# Schematic_Arduino-UNO-shield-for-program.net
KiCad netlist of a schematic drawn in EasyEDA
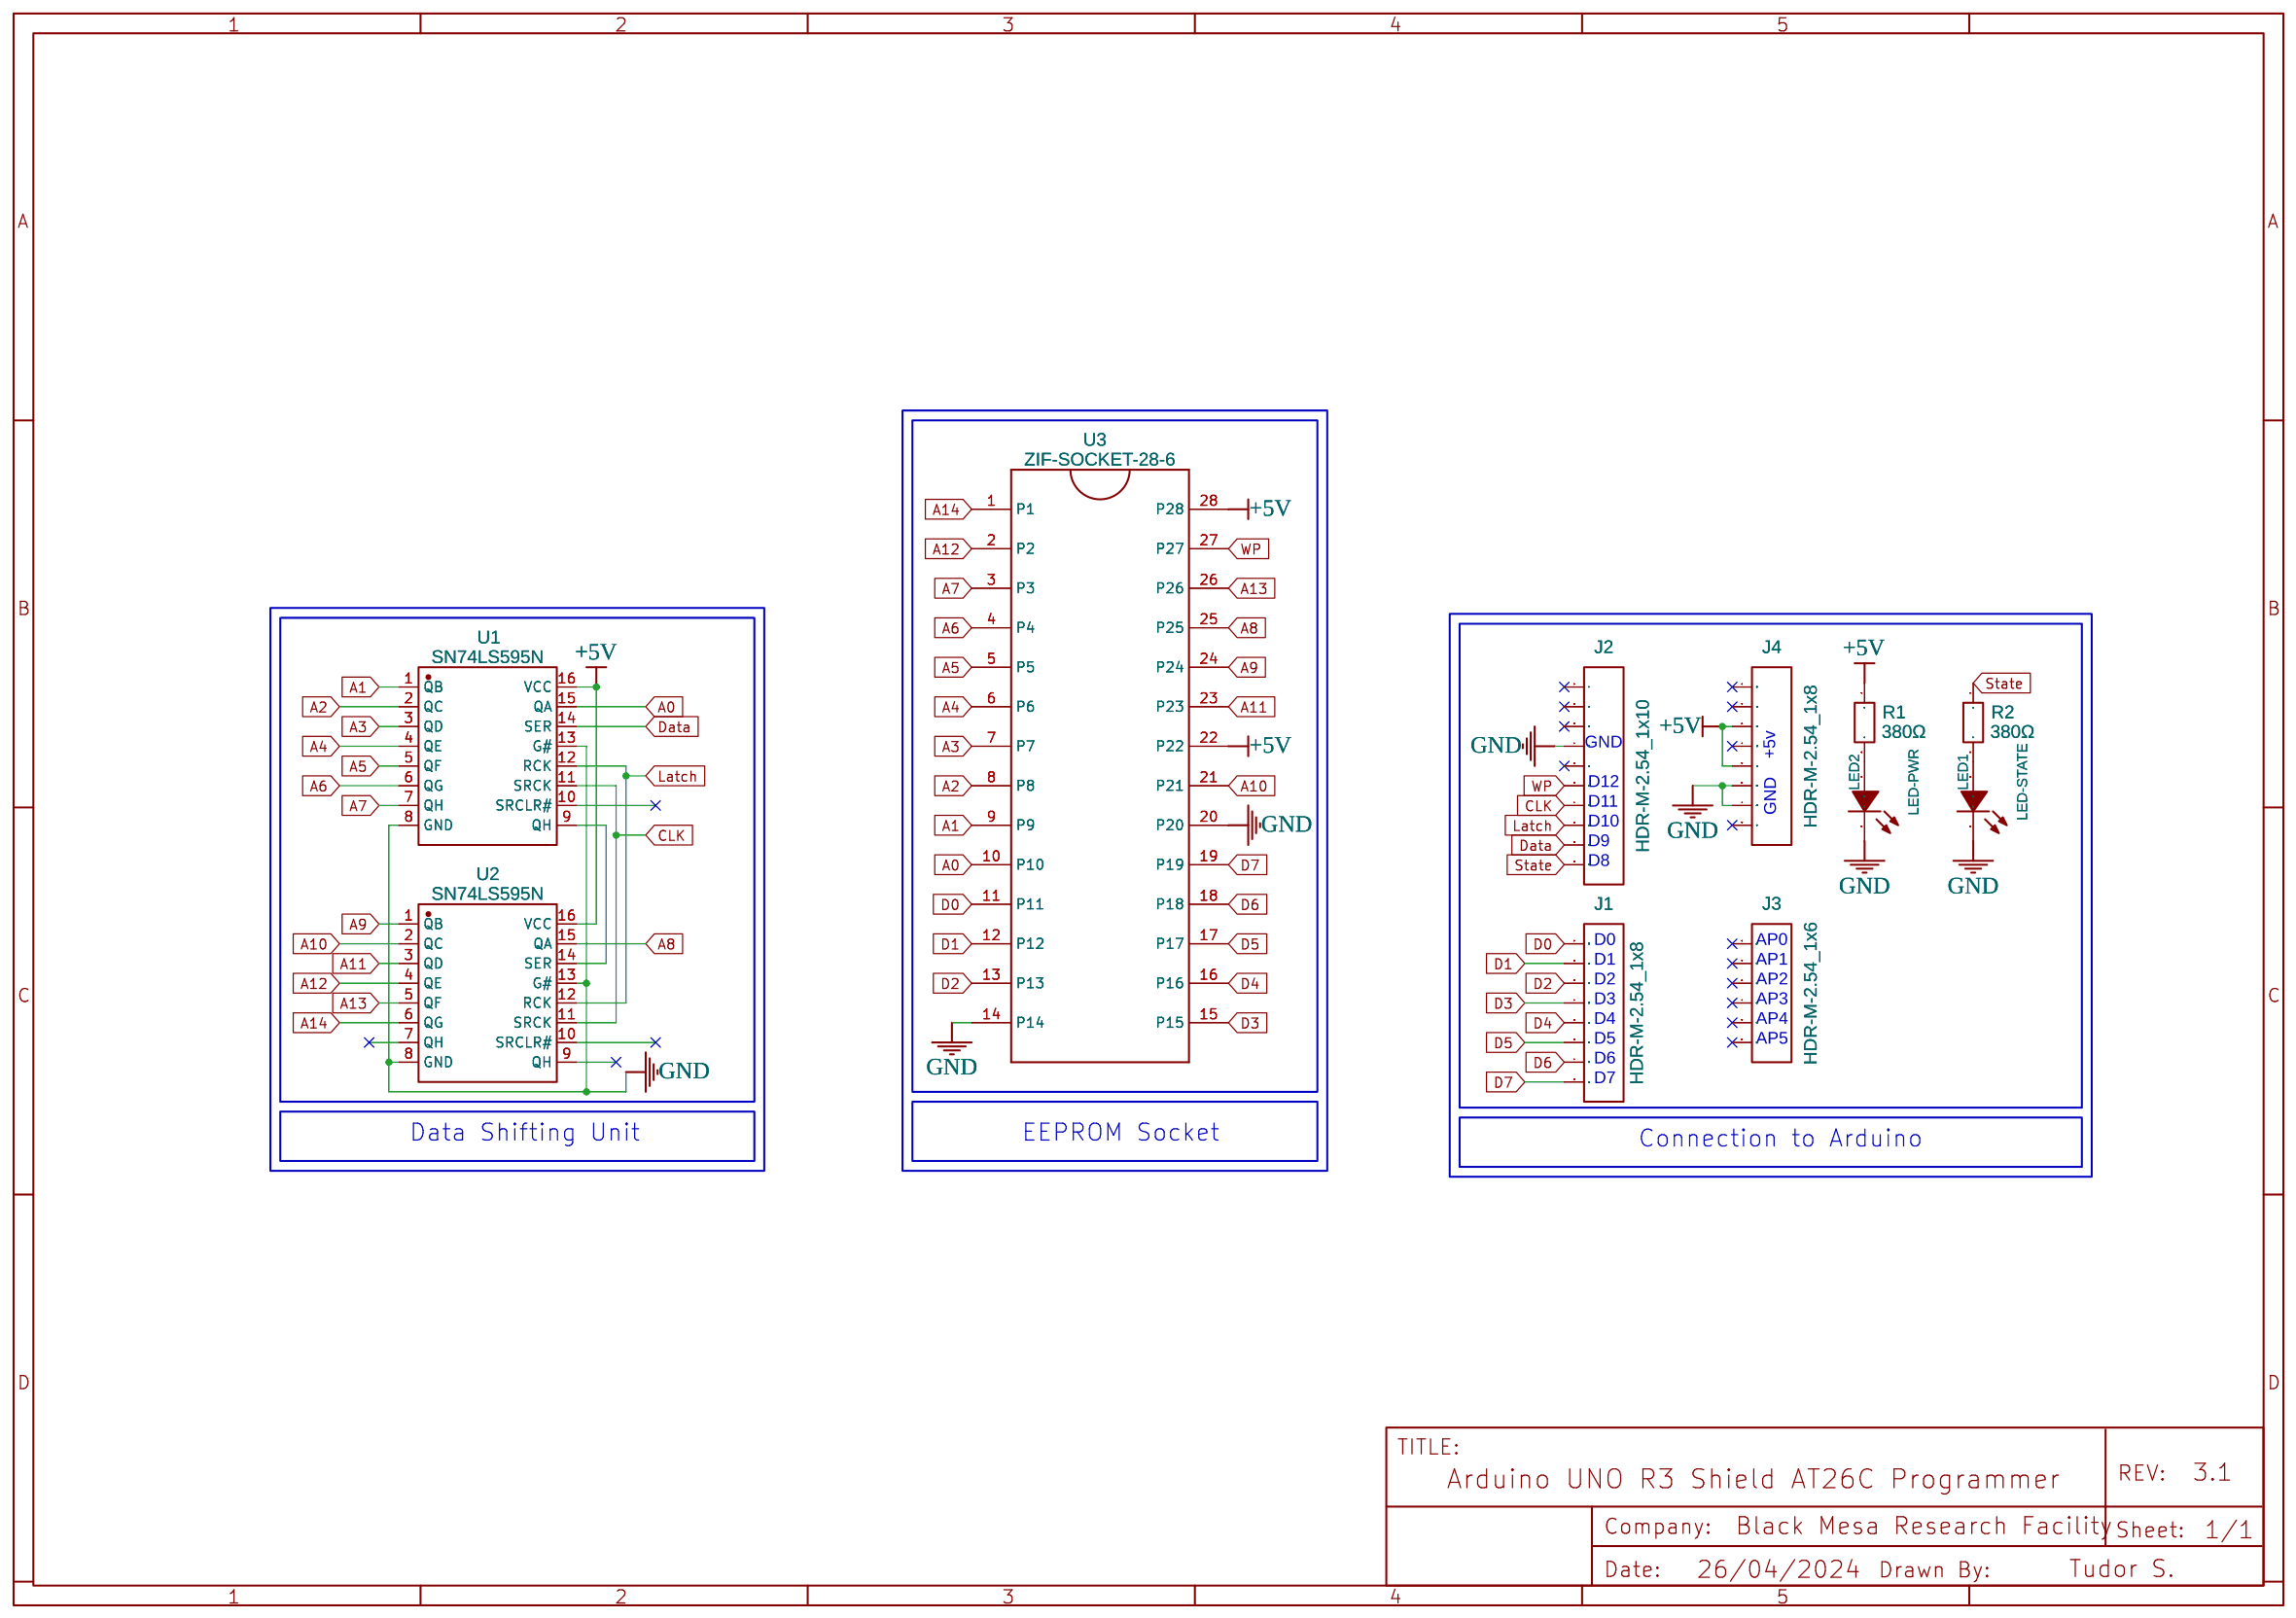
[diagram p0: schematic sheet]

(export (version "E")
  (design (tool "Eeschema 10.0.6"))
  (components
    (comp (ref "J1") (value "HDR-M-2.54_1x8") (libsource (lib "") (part "HDR-M-2.54_1x8")))
    (comp (ref "J2") (value "HDR-M-2.54_1x10") (libsource (lib "") (part "HDR-M-2.54_1x10")))
    (comp (ref "J3") (value "HDR-M-2.54_1x6") (libsource (lib "") (part "HDR-M-2.54_1x6")))
    (comp (ref "J4") (value "HDR-M-2.54_1x8") (libsource (lib "") (part "HDR-M-2.54_1x8_1")))
    (comp (ref "LED1")
      (value "LED-STATE")
      (fields
        (field (name "Manufacturer Part") "19-217/R6C-AL1M2VY/3T")
        (field (name "Manufacturer") "EVERLIGHT(台湾亿光)")
      )
      (libsource (lib "") (part "LED-0603_R"))
    )
    (comp (ref "LED2")
      (value "LED-PWR")
      (fields
        (field (name "Manufacturer Part") "19-217/R6C-AL1M2VY/3T")
        (field (name "Manufacturer") "EVERLIGHT(台湾亿光)")
      )
      (libsource (lib "") (part "LED-0603_R"))
    )
    (comp (ref "R1") (value "380Ω") (libsource (lib "") (part "R_AXIAL-0.4_EU")))
    (comp (ref "R2") (value "380Ω") (libsource (lib "") (part "R_AXIAL-0.4_EU")))
    (comp (ref "U1")
      (value "SN74LS595N")
      (fields (field (name "Manufacturer") "TI(德州仪器)"))
      (libsource (lib "") (part "SN74LS595N"))
    )
    (comp (ref "U2")
      (value "SN74LS595N")
      (fields (field (name "Manufacturer") "TI(德州仪器)"))
      (libsource (lib "") (part "SN74LS595N"))
    )
    (comp (ref "U3")
      (value "ZIF-SOCKET-28-6")
      (fields (field (name "Manufacturer Part") "ZIFSOCKET-28-6"))
      (libsource (lib "") (part "ZIF-SOCKET-28-6"))
    )
  )
  (nets
    (net (code "1") (name "+5V") (class "Default")
      (node (ref "J4") (pin "3") (pinfunction "RESET_3") (pintype "unspecified"))
      (node (ref "J4") (pin "5") (pinfunction "+5V_5") (pintype "unspecified"))
      (node (ref "R1") (pin "1") (pinfunction "1_1") (pintype "unspecified"))
      (node (ref "U1") (pin "16") (pinfunction "VCC_16") (pintype "unspecified"))
      (node (ref "U2") (pin "16") (pinfunction "VCC_16") (pintype "unspecified"))
      (node (ref "U3") (pin "22") (pinfunction "P22_22") (pintype "unspecified"))
      (node (ref "U3") (pin "28") (pinfunction "P28_28") (pintype "unspecified"))
    )
    (net (code "2") (name "A0") (class "Default")
      (node (ref "U1") (pin "15") (pinfunction "QA_15") (pintype "unspecified"))
      (node (ref "U3") (pin "10") (pinfunction "P10_10") (pintype "unspecified"))
    )
    (net (code "3") (name "A1") (class "Default")
      (node (ref "U1") (pin "1") (pinfunction "QB_1") (pintype "unspecified"))
      (node (ref "U3") (pin "9") (pinfunction "P9_9") (pintype "unspecified"))
    )
    (net (code "4") (name "A2") (class "Default")
      (node (ref "U1") (pin "2") (pinfunction "QC_2") (pintype "unspecified"))
      (node (ref "U3") (pin "8") (pinfunction "P8_8") (pintype "unspecified"))
    )
    (net (code "5") (name "A3") (class "Default")
      (node (ref "U1") (pin "3") (pinfunction "QD_3") (pintype "unspecified"))
      (node (ref "U3") (pin "7") (pinfunction "P7_7") (pintype "unspecified"))
    )
    (net (code "6") (name "A4") (class "Default")
      (node (ref "U1") (pin "4") (pinfunction "QE_4") (pintype "unspecified"))
      (node (ref "U3") (pin "6") (pinfunction "P6_6") (pintype "unspecified"))
    )
    (net (code "7") (name "A5") (class "Default")
      (node (ref "U1") (pin "5") (pinfunction "QF_5") (pintype "unspecified"))
      (node (ref "U3") (pin "5") (pinfunction "P5_5") (pintype "unspecified"))
    )
    (net (code "8") (name "A6") (class "Default")
      (node (ref "U1") (pin "6") (pinfunction "QG_6") (pintype "unspecified"))
      (node (ref "U3") (pin "4") (pinfunction "P4_4") (pintype "unspecified"))
    )
    (net (code "9") (name "A7") (class "Default")
      (node (ref "U1") (pin "7") (pinfunction "QH_7") (pintype "unspecified"))
      (node (ref "U3") (pin "3") (pinfunction "P3_3") (pintype "unspecified"))
    )
    (net (code "10") (name "A8") (class "Default")
      (node (ref "U2") (pin "15") (pinfunction "QA_15") (pintype "unspecified"))
      (node (ref "U3") (pin "25") (pinfunction "P25_25") (pintype "unspecified"))
    )
    (net (code "11") (name "A9") (class "Default")
      (node (ref "U2") (pin "1") (pinfunction "QB_1") (pintype "unspecified"))
      (node (ref "U3") (pin "24") (pinfunction "P24_24") (pintype "unspecified"))
    )
    (net (code "12") (name "A10") (class "Default")
      (node (ref "U2") (pin "2") (pinfunction "QC_2") (pintype "unspecified"))
      (node (ref "U3") (pin "21") (pinfunction "P21_21") (pintype "unspecified"))
    )
    (net (code "13") (name "A11") (class "Default")
      (node (ref "U2") (pin "3") (pinfunction "QD_3") (pintype "unspecified"))
      (node (ref "U3") (pin "23") (pinfunction "P23_23") (pintype "unspecified"))
    )
    (net (code "14") (name "A12") (class "Default")
      (node (ref "U2") (pin "4") (pinfunction "QE_4") (pintype "unspecified"))
      (node (ref "U3") (pin "2") (pinfunction "P2_2") (pintype "unspecified"))
    )
    (net (code "15") (name "A13") (class "Default")
      (node (ref "U2") (pin "5") (pinfunction "QF_5") (pintype "unspecified"))
      (node (ref "U3") (pin "26") (pinfunction "P26_26") (pintype "unspecified"))
    )
    (net (code "16") (name "A14") (class "Default")
      (node (ref "U2") (pin "6") (pinfunction "QG_6") (pintype "unspecified"))
      (node (ref "U3") (pin "1") (pinfunction "P1_1") (pintype "unspecified"))
    )
    (net (code "17") (name "CLK") (class "Default")
      (node (ref "J2") (pin "7") (pinfunction "D11_7") (pintype "unspecified"))
      (node (ref "U1") (pin "11") (pinfunction "SRCK_11") (pintype "unspecified"))
      (node (ref "U2") (pin "11") (pinfunction "SRCK_11") (pintype "unspecified"))
    )
    (net (code "18") (name "D0") (class "Default")
      (node (ref "J1") (pin "1") (pinfunction "D0_1") (pintype "unspecified"))
      (node (ref "U3") (pin "11") (pinfunction "P11_11") (pintype "unspecified"))
    )
    (net (code "19") (name "D1") (class "Default")
      (node (ref "J1") (pin "2") (pinfunction "D1_2") (pintype "unspecified"))
      (node (ref "U3") (pin "12") (pinfunction "P12_12") (pintype "unspecified"))
    )
    (net (code "20") (name "D2") (class "Default")
      (node (ref "J1") (pin "3") (pinfunction "D2_3") (pintype "unspecified"))
      (node (ref "U3") (pin "13") (pinfunction "P13_13") (pintype "unspecified"))
    )
    (net (code "21") (name "D3") (class "Default")
      (node (ref "J1") (pin "4") (pinfunction "D3_4") (pintype "unspecified"))
      (node (ref "U3") (pin "15") (pinfunction "P15_15") (pintype "unspecified"))
    )
    (net (code "22") (name "D4") (class "Default")
      (node (ref "J1") (pin "5") (pinfunction "D4_5") (pintype "unspecified"))
      (node (ref "U3") (pin "16") (pinfunction "P16_16") (pintype "unspecified"))
    )
    (net (code "23") (name "D5") (class "Default")
      (node (ref "J1") (pin "6") (pinfunction "D5_6") (pintype "unspecified"))
      (node (ref "U3") (pin "17") (pinfunction "P17_17") (pintype "unspecified"))
    )
    (net (code "24") (name "D6") (class "Default")
      (node (ref "J1") (pin "7") (pinfunction "D6_7") (pintype "unspecified"))
      (node (ref "U3") (pin "18") (pinfunction "P18_18") (pintype "unspecified"))
    )
    (net (code "25") (name "D7") (class "Default")
      (node (ref "J1") (pin "8") (pinfunction "D7_8") (pintype "unspecified"))
      (node (ref "U3") (pin "19") (pinfunction "P19_19") (pintype "unspecified"))
    )
    (net (code "26") (name "Data") (class "Default")
      (node (ref "J2") (pin "9") (pinfunction "D9_9") (pintype "unspecified"))
      (node (ref "U1") (pin "14") (pinfunction "SER_14") (pintype "unspecified"))
    )
    (net (code "27") (name "GND") (class "Default")
      (node (ref "J2") (pin "4") (pinfunction "GND_4") (pintype "unspecified"))
      (node (ref "J4") (pin "6") (pinfunction "GND_6") (pintype "unspecified"))
      (node (ref "J4") (pin "7") (pinfunction "GND_7") (pintype "unspecified"))
      (node (ref "LED1") (pin "2") (pinfunction "2_2") (pintype "unspecified"))
      (node (ref "LED2") (pin "2") (pinfunction "2_2") (pintype "unspecified"))
      (node (ref "U1") (pin "13") (pinfunction "G#_13") (pintype "unspecified"))
      (node (ref "U1") (pin "8") (pinfunction "GND_8") (pintype "unspecified"))
      (node (ref "U2") (pin "13") (pinfunction "G#_13") (pintype "unspecified"))
      (node (ref "U2") (pin "8") (pinfunction "GND_8") (pintype "unspecified"))
      (node (ref "U3") (pin "14") (pinfunction "P14_14") (pintype "unspecified"))
      (node (ref "U3") (pin "20") (pinfunction "P20_20") (pintype "unspecified"))
    )
    (net (code "28") (name "Latch") (class "Default")
      (node (ref "J2") (pin "8") (pinfunction "D10_8") (pintype "unspecified"))
      (node (ref "U1") (pin "12") (pinfunction "RCK_12") (pintype "unspecified"))
      (node (ref "U2") (pin "12") (pinfunction "RCK_12") (pintype "unspecified"))
    )
    (net (code "29") (name "Net-(LED1-Pad1)") (class "Default")
      (node (ref "LED1") (pin "1") (pinfunction "1_1") (pintype "unspecified"))
      (node (ref "R2") (pin "2") (pinfunction "2_2") (pintype "unspecified"))
    )
    (net (code "30") (name "Net-(LED2-Pad1)") (class "Default")
      (node (ref "LED2") (pin "1") (pinfunction "1_1") (pintype "unspecified"))
      (node (ref "R1") (pin "2") (pinfunction "2_2") (pintype "unspecified"))
    )
    (net (code "31") (name "Net-(U2-SER)") (class "Default")
      (node (ref "U1") (pin "9") (pinfunction "QH_9") (pintype "unspecified"))
      (node (ref "U2") (pin "14") (pinfunction "SER_14") (pintype "unspecified"))
    )
    (net (code "32") (name "State") (class "Default")
      (node (ref "J2") (pin "10") (pinfunction "D8_10") (pintype "unspecified"))
      (node (ref "R2") (pin "1") (pinfunction "1_1") (pintype "unspecified"))
    )
    (net (code "33") (name "WP") (class "Default")
      (node (ref "J2") (pin "6") (pinfunction "D12_6") (pintype "unspecified"))
      (node (ref "U3") (pin "27") (pinfunction "P27_27") (pintype "unspecified"))
    )
    (net (code "34") (name "unconnected-(J2-AREF-Pad3)") (class "Default")
      (node (ref "J2") (pin "3") (pinfunction "AREF_3") (pintype "unspecified+no_connect"))
    )
    (net (code "35") (name "unconnected-(J2-D13-Pad5)") (class "Default")
      (node (ref "J2") (pin "5") (pinfunction "D13_5") (pintype "unspecified+no_connect"))
    )
    (net (code "36") (name "unconnected-(J2-Pad1)") (class "Default")
      (node (ref "J2") (pin "1") (pinfunction "1_1") (pintype "unspecified+no_connect"))
    )
    (net (code "37") (name "unconnected-(J2-Pad2)") (class "Default")
      (node (ref "J2") (pin "2") (pinfunction "2_2") (pintype "unspecified+no_connect"))
    )
    (net (code "38") (name "unconnected-(J3-S0-Pad1)") (class "Default")
      (node (ref "J3") (pin "1") (pinfunction "S0_1") (pintype "input+no_connect"))
    )
    (net (code "39") (name "unconnected-(J3-S1-Pad2)") (class "Default")
      (node (ref "J3") (pin "2") (pinfunction "S1_2") (pintype "input+no_connect"))
    )
    (net (code "40") (name "unconnected-(J3-S2-Pad3)") (class "Default")
      (node (ref "J3") (pin "3") (pinfunction "S2_3") (pintype "input+no_connect"))
    )
    (net (code "41") (name "unconnected-(J3-S3-Pad4)") (class "Default")
      (node (ref "J3") (pin "4") (pinfunction "S3_4") (pintype "input+no_connect"))
    )
    (net (code "42") (name "unconnected-(J3-S4-Pad5)") (class "Default")
      (node (ref "J3") (pin "5") (pinfunction "S4_5") (pintype "input+no_connect"))
    )
    (net (code "43") (name "unconnected-(J3-S5-Pad6)") (class "Default")
      (node (ref "J3") (pin "6") (pinfunction "S5_6") (pintype "input+no_connect"))
    )
    (net (code "44") (name "unconnected-(J4-+3.3V-Pad4)") (class "Default")
      (node (ref "J4") (pin "4") (pinfunction "+3.3V_4") (pintype "unspecified+no_connect"))
    )
    (net (code "45") (name "unconnected-(J4-+5V-Pad2)") (class "Default")
      (node (ref "J4") (pin "2") (pinfunction "+5V_2") (pintype "unspecified+no_connect"))
    )
    (net (code "46") (name "unconnected-(J4-J2_1-Pad1)") (class "Default")
      (node (ref "J4") (pin "1") (pinfunction "J2_1_1") (pintype "unspecified+no_connect"))
    )
    (net (code "47") (name "unconnected-(J4-VIN-Pad8)") (class "Default")
      (node (ref "J4") (pin "8") (pinfunction "VIN_8") (pintype "unspecified+no_connect"))
    )
    (net (code "48") (name "unconnected-(U1-SRCLR#-Pad10)") (class "Default")
      (node (ref "U1") (pin "10") (pinfunction "SRCLR#_10") (pintype "unspecified+no_connect"))
    )
    (net (code "49") (name "unconnected-(U2-QH-Pad7)") (class "Default")
      (node (ref "U2") (pin "7") (pinfunction "QH_7") (pintype "unspecified+no_connect"))
    )
    (net (code "50") (name "unconnected-(U2-QH-Pad9)") (class "Default")
      (node (ref "U2") (pin "9") (pinfunction "QH_9") (pintype "unspecified+no_connect"))
    )
    (net (code "51") (name "unconnected-(U2-SRCLR#-Pad10)") (class "Default")
      (node (ref "U2") (pin "10") (pinfunction "SRCLR#_10") (pintype "unspecified+no_connect"))
    )
  )
)
